# dac-power.net
KiCad netlist of a schematic drawn in Altium Designer
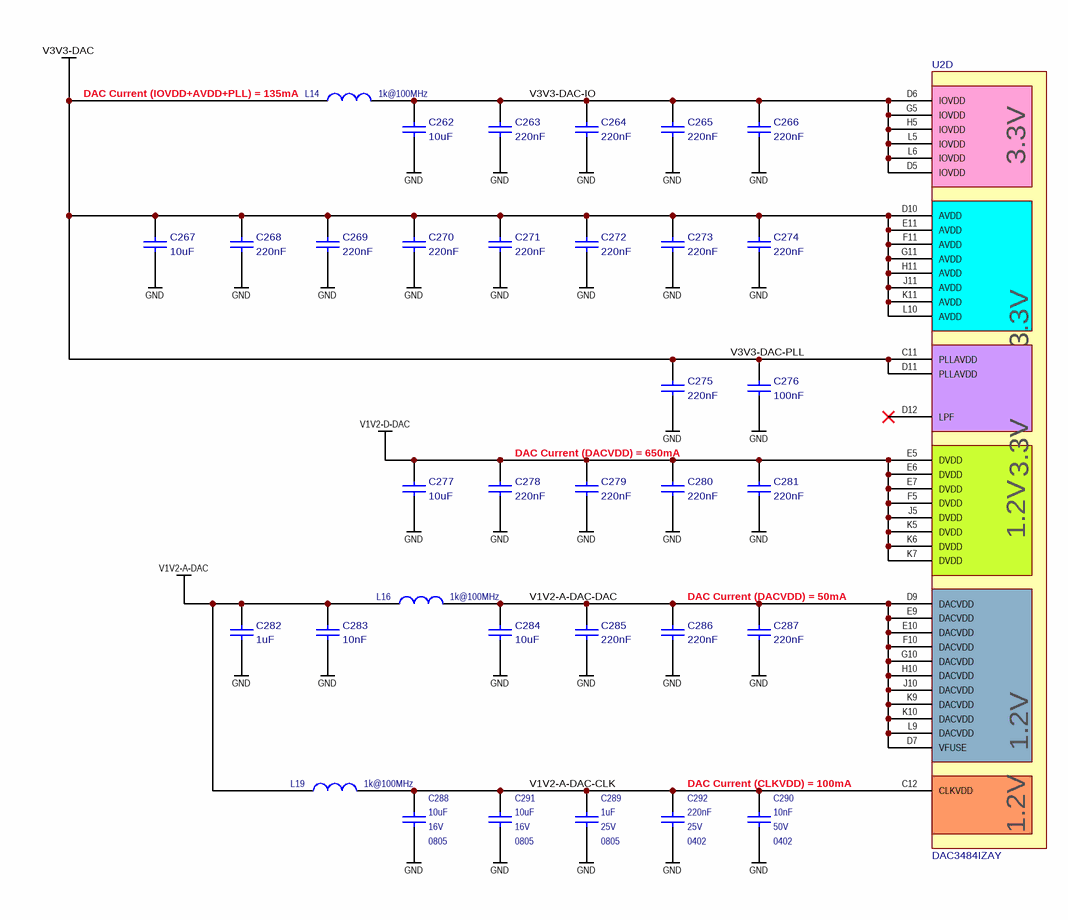
[diagram p0: dac-power.SchDoc]

(export (version "E")
  (design (tool "Eeschema 10.0.6"))
  (components
    (comp (ref "C262")
      (value "10uF")
      (footprint "CAPC200X125X145L45N")
      (description "Ceramic Capacitor 10uF ±10% 16V X7R 0805")
      (fields (field (name "MANUFACTURER") "Samsung") (field (name "TOLERANCE") "±10%"))
      (libsource (lib "capacitors") (part "CAP"))
    )
    (comp (ref "C263")
      (value "220nF")
      (footprint "CAPC100X50X55L25N")
      (description "Ceramic Capacitor 220nF ±10% 25V X7R 0402")
      (fields (field (name "MANUFACTURER") "TDK") (field (name "TOLERANCE") "±10%"))
      (libsource (lib "capacitors") (part "CAP"))
    )
    (comp (ref "C264")
      (value "220nF")
      (footprint "CAPC100X50X55L25N")
      (description "Ceramic Capacitor 220nF ±10% 25V X7R 0402")
      (fields (field (name "MANUFACTURER") "TDK") (field (name "TOLERANCE") "±10%"))
      (libsource (lib "capacitors") (part "CAP"))
    )
    (comp (ref "C265")
      (value "220nF")
      (footprint "CAPC100X50X55L25N")
      (description "Ceramic Capacitor 220nF ±10% 25V X7R 0402")
      (fields (field (name "MANUFACTURER") "TDK") (field (name "TOLERANCE") "±10%"))
      (libsource (lib "capacitors") (part "CAP"))
    )
    (comp (ref "C266")
      (value "220nF")
      (footprint "CAPC100X50X55L25N")
      (description "Ceramic Capacitor 220nF ±10% 25V X7R 0402")
      (fields (field (name "MANUFACTURER") "TDK") (field (name "TOLERANCE") "±10%"))
      (libsource (lib "capacitors") (part "CAP"))
    )
    (comp (ref "C267")
      (value "10uF")
      (footprint "CAPC200X125X145L45N")
      (description "Ceramic Capacitor 10uF ±10% 16V X7R 0805")
      (fields (field (name "MANUFACTURER") "Samsung") (field (name "TOLERANCE") "±10%"))
      (libsource (lib "capacitors") (part "CAP"))
    )
    (comp (ref "C268")
      (value "220nF")
      (footprint "CAPC100X50X55L25N")
      (description "Ceramic Capacitor 220nF ±10% 25V X7R 0402")
      (fields (field (name "MANUFACTURER") "TDK") (field (name "TOLERANCE") "±10%"))
      (libsource (lib "capacitors") (part "CAP"))
    )
    (comp (ref "C269")
      (value "220nF")
      (footprint "CAPC100X50X55L25N")
      (description "Ceramic Capacitor 220nF ±10% 25V X7R 0402")
      (fields (field (name "MANUFACTURER") "TDK") (field (name "TOLERANCE") "±10%"))
      (libsource (lib "capacitors") (part "CAP"))
    )
    (comp (ref "C270")
      (value "220nF")
      (footprint "CAPC100X50X55L25N")
      (description "Ceramic Capacitor 220nF ±10% 25V X7R 0402")
      (fields (field (name "MANUFACTURER") "TDK") (field (name "TOLERANCE") "±10%"))
      (libsource (lib "capacitors") (part "CAP"))
    )
    (comp (ref "C271")
      (value "220nF")
      (footprint "CAPC100X50X55L25N")
      (description "Ceramic Capacitor 220nF ±10% 25V X7R 0402")
      (fields (field (name "MANUFACTURER") "TDK") (field (name "TOLERANCE") "±10%"))
      (libsource (lib "capacitors") (part "CAP"))
    )
    (comp (ref "C272")
      (value "220nF")
      (footprint "CAPC100X50X55L25N")
      (description "Ceramic Capacitor 220nF ±10% 25V X7R 0402")
      (fields (field (name "MANUFACTURER") "TDK") (field (name "TOLERANCE") "±10%"))
      (libsource (lib "capacitors") (part "CAP"))
    )
    (comp (ref "C273")
      (value "220nF")
      (footprint "CAPC100X50X55L25N")
      (description "Ceramic Capacitor 220nF ±10% 25V X7R 0402")
      (fields (field (name "MANUFACTURER") "TDK") (field (name "TOLERANCE") "±10%"))
      (libsource (lib "capacitors") (part "CAP"))
    )
    (comp (ref "C274")
      (value "220nF")
      (footprint "CAPC100X50X55L25N")
      (description "Ceramic Capacitor 220nF ±10% 25V X7R 0402")
      (fields (field (name "MANUFACTURER") "TDK") (field (name "TOLERANCE") "±10%"))
      (libsource (lib "capacitors") (part "CAP"))
    )
    (comp (ref "C275")
      (value "220nF")
      (footprint "CAPC100X50X55L25N")
      (description "Ceramic Capacitor 220nF ±10% 25V X7R 0402")
      (fields (field (name "MANUFACTURER") "TDK") (field (name "TOLERANCE") "±10%"))
      (libsource (lib "capacitors") (part "CAP"))
    )
    (comp (ref "C276")
      (value "100nF")
      (footprint "CAPC100X50X55L25N")
      (description "Ceramic Capacitor 100nF ±10% 25V X7R 0402")
      (fields (field (name "MANUFACTURER") "Yageo") (field (name "TOLERANCE") "±10%"))
      (libsource (lib "capacitors") (part "CAP"))
    )
    (comp (ref "C277")
      (value "10uF")
      (footprint "CAPC200X125X145L45N")
      (description "Ceramic Capacitor 10uF ±10% 16V X7R 0805")
      (fields (field (name "MANUFACTURER") "Samsung") (field (name "TOLERANCE") "±10%"))
      (libsource (lib "capacitors") (part "CAP"))
    )
    (comp (ref "C278")
      (value "220nF")
      (footprint "CAPC100X50X55L25N")
      (description "Ceramic Capacitor 220nF ±10% 25V X7R 0402")
      (fields (field (name "MANUFACTURER") "TDK") (field (name "TOLERANCE") "±10%"))
      (libsource (lib "capacitors") (part "CAP"))
    )
    (comp (ref "C279")
      (value "220nF")
      (footprint "CAPC100X50X55L25N")
      (description "Ceramic Capacitor 220nF ±10% 25V X7R 0402")
      (fields (field (name "MANUFACTURER") "TDK") (field (name "TOLERANCE") "±10%"))
      (libsource (lib "capacitors") (part "CAP"))
    )
    (comp (ref "C280")
      (value "220nF")
      (footprint "CAPC100X50X55L25N")
      (description "Ceramic Capacitor 220nF ±10% 25V X7R 0402")
      (fields (field (name "MANUFACTURER") "TDK") (field (name "TOLERANCE") "±10%"))
      (libsource (lib "capacitors") (part "CAP"))
    )
    (comp (ref "C281")
      (value "220nF")
      (footprint "CAPC100X50X55L25N")
      (description "Ceramic Capacitor 220nF ±10% 25V X7R 0402")
      (fields (field (name "MANUFACTURER") "TDK") (field (name "TOLERANCE") "±10%"))
      (libsource (lib "capacitors") (part "CAP"))
    )
    (comp (ref "C282")
      (value "1uF")
      (footprint "CAPC200X125X145L45N")
      (description "Ceramic Capacitor 1uF ±10% 25V X7R 0805")
      (fields (field (name "MANUFACTURER") "Taiyo Yuden") (field (name "TOLERANCE") "±10%"))
      (libsource (lib "capacitors") (part "CAP"))
    )
    (comp (ref "C283")
      (value "10nF")
      (footprint "CAPC100X50X55L25N")
      (description "Ceramic Capacitor 10nF ±10% 50V X7R 0402")
      (fields (field (name "MANUFACTURER") "Murata") (field (name "TOLERANCE") "±10%"))
      (libsource (lib "capacitors") (part "CAP"))
    )
    (comp (ref "C284")
      (value "10uF")
      (footprint "CAPC200X125X145L45N")
      (description "Ceramic Capacitor 10uF ±10% 16V X7R 0805")
      (fields (field (name "MANUFACTURER") "Samsung") (field (name "TOLERANCE") "±10%"))
      (libsource (lib "capacitors") (part "CAP"))
    )
    (comp (ref "C285")
      (value "220nF")
      (footprint "CAPC100X50X55L25N")
      (description "Ceramic Capacitor 220nF ±10% 25V X7R 0402")
      (fields (field (name "MANUFACTURER") "TDK") (field (name "TOLERANCE") "±10%"))
      (libsource (lib "capacitors") (part "CAP"))
    )
    (comp (ref "C286")
      (value "220nF")
      (footprint "CAPC100X50X55L25N")
      (description "Ceramic Capacitor 220nF ±10% 25V X7R 0402")
      (fields (field (name "MANUFACTURER") "TDK") (field (name "TOLERANCE") "±10%"))
      (libsource (lib "capacitors") (part "CAP"))
    )
    (comp (ref "C287")
      (value "220nF")
      (footprint "CAPC100X50X55L25N")
      (description "Ceramic Capacitor 220nF ±10% 25V X7R 0402")
      (fields (field (name "MANUFACTURER") "TDK") (field (name "TOLERANCE") "±10%"))
      (libsource (lib "capacitors") (part "CAP"))
    )
    (comp (ref "C288")
      (value "10uF")
      (footprint "generic:CAPC2012X145N")
      (description "Ceramic Capacitor 10uF ±20% 16V X7R 0805")
      (fields
        (field (name "MANUFACTURER") "Taiyo Yuden")
        (field (name "VOLTAGE") "16V")
        (field (name "PACKAGE") "0805")
        (field (name "TOLERANCE") "±20%")
      )
      (libsource (lib "generic") (part "CAP 0603"))
    )
    (comp (ref "C289")
      (value "1uF")
      (footprint "CAPC200X125X145L45N")
      (description "Ceramic Capacitor 1uF ±10% 25V X7R 0805")
      (fields
        (field (name "VOLTAGE") "25V")
        (field (name "MANUFACTURER") "Taiyo Yuden")
        (field (name "PACKAGE") "0805")
        (field (name "TOLERANCE") "±10%")
      )
      (libsource (lib "Graviton") (part "CAP 0402"))
    )
    (comp (ref "C290")
      (value "10nF")
      (footprint "CAPC100X50X55L25N")
      (description "Ceramic Capacitor 10nF ±10% 50V X7R 0402")
      (fields
        (field (name "VOLTAGE") "50V")
        (field (name "MANUFACTURER") "Murata")
        (field (name "PACKAGE") "0402")
        (field (name "TOLERANCE") "±10%")
      )
      (libsource (lib "Graviton") (part "CAP 0402"))
    )
    (comp (ref "C291")
      (value "10uF")
      (footprint "generic:CAPC2012X145N")
      (description "Ceramic Capacitor 10uF ±20% 16V X7R 0805")
      (fields
        (field (name "MANUFACTURER") "Taiyo Yuden")
        (field (name "VOLTAGE") "16V")
        (field (name "PACKAGE") "0805")
        (field (name "TOLERANCE") "±20%")
      )
      (libsource (lib "generic") (part "CAP 0603"))
    )
    (comp (ref "C292")
      (value "220nF")
      (footprint "CAPC100X50X55L25N")
      (description "Ceramic Capacitor 220nF ±10% 25V X7R 0402")
      (fields
        (field (name "VOLTAGE") "25V")
        (field (name "MANUFACTURER") "TDK")
        (field (name "PACKAGE") "0402")
        (field (name "TOLERANCE") "±10%")
      )
      (libsource (lib "Graviton") (part "CAP 0402"))
    )
    (comp (ref "L14")
      (value "1k@100MHz")
      (footprint "generic:1806")
      (description "Ferrite Bead 1k@100MHz 1.5A 1806")
      (fields (field (name "MANUFACTURER") "Murata") (field (name "Comment") "BLM41PG102SN1L"))
      (libsource (lib "*") (part "INDUCTANCE1"))
    )
    (comp (ref "L16")
      (value "1k@100MHz")
      (footprint "generic:1806")
      (description "Ferrite Bead 1k@100MHz 1.5A 1806")
      (fields (field (name "MANUFACTURER") "Murata") (field (name "Comment") "BLM41PG102SN1L"))
      (libsource (lib "*") (part "INDUCTANCE1"))
    )
    (comp (ref "L19")
      (value "1k@100MHz")
      (footprint "generic:1806")
      (description "Ferrite Bead 1k@100MHz 1.5A 1806")
      (fields (field (name "MANUFACTURER") "Murata") (field (name "Comment") "BLM41PG102SN1L"))
      (libsource (lib "*") (part "INDUCTANCE1"))
    )
    (comp (ref "U2")
      (value "DAC3484IZAY")
      (footprint "ZAY-BGA-196")
      (description "High Speed Quad DAC, 16-bit, 1.25GSPS")
      (fields (field (name "MANUFACTURER") "Texas Instruments"))
      (libsource (lib "ti") (part "DAC3484IZAY"))
    )
  )
  (nets
    (net (code "1") (name "/V1V2-A-DAC-CLK") (class "Default")
      (node (ref "C288") (pin "2") (pinfunction "2_2") (pintype "passive"))
      (node (ref "C289") (pin "2") (pinfunction "2_2") (pintype "passive"))
      (node (ref "C290") (pin "2") (pinfunction "2_2") (pintype "passive"))
      (node (ref "C291") (pin "2") (pinfunction "2_2") (pintype "passive"))
      (node (ref "C292") (pin "2") (pinfunction "2_2") (pintype "passive"))
      (node (ref "L19") (pin "2") (pinfunction "2_2") (pintype "passive"))
      (node (ref "U2") (pin "C12") (pinfunction "CLKVDD_C12") (pintype "power_in"))
    )
    (net (code "2") (name "/V1V2-A-DAC-DAC") (class "Default")
      (node (ref "C284") (pin "1") (pinfunction "1_1") (pintype "passive"))
      (node (ref "C285") (pin "1") (pinfunction "1_1") (pintype "passive"))
      (node (ref "C286") (pin "1") (pinfunction "1_1") (pintype "passive"))
      (node (ref "C287") (pin "1") (pinfunction "1_1") (pintype "passive"))
      (node (ref "L16") (pin "2") (pinfunction "2_2") (pintype "passive"))
      (node (ref "U2") (pin "D7") (pinfunction "VFUSE_D7") (pintype "passive"))
      (node (ref "U2") (pin "D9") (pinfunction "DACVDD_D9") (pintype "power_in"))
      (node (ref "U2") (pin "E10") (pinfunction "DACVDD_E10") (pintype "power_in"))
      (node (ref "U2") (pin "E9") (pinfunction "DACVDD_E9") (pintype "power_in"))
      (node (ref "U2") (pin "F10") (pinfunction "DACVDD_F10") (pintype "power_in"))
      (node (ref "U2") (pin "G10") (pinfunction "DACVDD_G10") (pintype "power_in"))
      (node (ref "U2") (pin "H10") (pinfunction "DACVDD_H10") (pintype "power_in"))
      (node (ref "U2") (pin "J10") (pinfunction "DACVDD_J10") (pintype "power_in"))
      (node (ref "U2") (pin "K10") (pinfunction "DACVDD_K10") (pintype "power_in"))
      (node (ref "U2") (pin "K9") (pinfunction "DACVDD_K9") (pintype "power_in"))
      (node (ref "U2") (pin "L9") (pinfunction "DACVDD_L9") (pintype "power_in"))
    )
    (net (code "3") (name "/V3V3-DAC-IO") (class "Default")
      (node (ref "C262") (pin "1") (pinfunction "1_1") (pintype "passive"))
      (node (ref "C263") (pin "1") (pinfunction "1_1") (pintype "passive"))
      (node (ref "C264") (pin "1") (pinfunction "1_1") (pintype "passive"))
      (node (ref "C265") (pin "1") (pinfunction "1_1") (pintype "passive"))
      (node (ref "C266") (pin "1") (pinfunction "1_1") (pintype "passive"))
      (node (ref "L14") (pin "2") (pinfunction "2_2") (pintype "passive"))
      (node (ref "U2") (pin "D5") (pinfunction "IOVDD_D5") (pintype "power_in"))
      (node (ref "U2") (pin "D6") (pinfunction "IOVDD_D6") (pintype "power_in"))
      (node (ref "U2") (pin "G5") (pinfunction "IOVDD_G5") (pintype "power_in"))
      (node (ref "U2") (pin "H5") (pinfunction "IOVDD_H5") (pintype "power_in"))
      (node (ref "U2") (pin "L5") (pinfunction "IOVDD_L5") (pintype "power_in"))
      (node (ref "U2") (pin "L6") (pinfunction "IOVDD_L6") (pintype "power_in"))
    )
    (net (code "4") (name "GND") (class "Default")
      (node (ref "C262") (pin "2") (pinfunction "2_2") (pintype "passive"))
      (node (ref "C263") (pin "2") (pinfunction "2_2") (pintype "passive"))
      (node (ref "C264") (pin "2") (pinfunction "2_2") (pintype "passive"))
      (node (ref "C265") (pin "2") (pinfunction "2_2") (pintype "passive"))
      (node (ref "C266") (pin "2") (pinfunction "2_2") (pintype "passive"))
      (node (ref "C267") (pin "2") (pinfunction "2_2") (pintype "passive"))
      (node (ref "C268") (pin "2") (pinfunction "2_2") (pintype "passive"))
      (node (ref "C269") (pin "2") (pinfunction "2_2") (pintype "passive"))
      (node (ref "C270") (pin "2") (pinfunction "2_2") (pintype "passive"))
      (node (ref "C271") (pin "2") (pinfunction "2_2") (pintype "passive"))
      (node (ref "C272") (pin "2") (pinfunction "2_2") (pintype "passive"))
      (node (ref "C273") (pin "2") (pinfunction "2_2") (pintype "passive"))
      (node (ref "C274") (pin "2") (pinfunction "2_2") (pintype "passive"))
      (node (ref "C275") (pin "2") (pinfunction "2_2") (pintype "passive"))
      (node (ref "C276") (pin "2") (pinfunction "2_2") (pintype "passive"))
      (node (ref "C277") (pin "2") (pinfunction "2_2") (pintype "passive"))
      (node (ref "C278") (pin "2") (pinfunction "2_2") (pintype "passive"))
      (node (ref "C279") (pin "2") (pinfunction "2_2") (pintype "passive"))
      (node (ref "C280") (pin "2") (pinfunction "2_2") (pintype "passive"))
      (node (ref "C281") (pin "2") (pinfunction "2_2") (pintype "passive"))
      (node (ref "C282") (pin "2") (pinfunction "2_2") (pintype "passive"))
      (node (ref "C283") (pin "2") (pinfunction "2_2") (pintype "passive"))
      (node (ref "C284") (pin "2") (pinfunction "2_2") (pintype "passive"))
      (node (ref "C285") (pin "2") (pinfunction "2_2") (pintype "passive"))
      (node (ref "C286") (pin "2") (pinfunction "2_2") (pintype "passive"))
      (node (ref "C287") (pin "2") (pinfunction "2_2") (pintype "passive"))
      (node (ref "C288") (pin "1") (pinfunction "1_1") (pintype "passive"))
      (node (ref "C289") (pin "1") (pinfunction "1_1") (pintype "passive"))
      (node (ref "C290") (pin "1") (pinfunction "1_1") (pintype "passive"))
      (node (ref "C291") (pin "1") (pinfunction "1_1") (pintype "passive"))
      (node (ref "C292") (pin "1") (pinfunction "1_1") (pintype "passive"))
    )
    (net (code "5") (name "V1V2-A-DAC") (class "Default")
      (node (ref "C282") (pin "1") (pinfunction "1_1") (pintype "passive"))
      (node (ref "C283") (pin "1") (pinfunction "1_1") (pintype "passive"))
      (node (ref "L16") (pin "1") (pinfunction "1_1") (pintype "passive"))
      (node (ref "L19") (pin "1") (pinfunction "1_1") (pintype "passive"))
    )
    (net (code "6") (name "V1V2-D-DAC") (class "Default")
      (node (ref "C277") (pin "1") (pinfunction "1_1") (pintype "passive"))
      (node (ref "C278") (pin "1") (pinfunction "1_1") (pintype "passive"))
      (node (ref "C279") (pin "1") (pinfunction "1_1") (pintype "passive"))
      (node (ref "C280") (pin "1") (pinfunction "1_1") (pintype "passive"))
      (node (ref "C281") (pin "1") (pinfunction "1_1") (pintype "passive"))
      (node (ref "U2") (pin "E5") (pinfunction "DVDD_E5") (pintype "power_in"))
      (node (ref "U2") (pin "E6") (pinfunction "DVDD_E6") (pintype "power_in"))
      (node (ref "U2") (pin "E7") (pinfunction "DVDD_E7") (pintype "power_in"))
      (node (ref "U2") (pin "F5") (pinfunction "DVDD_F5") (pintype "power_in"))
      (node (ref "U2") (pin "J5") (pinfunction "DVDD_J5") (pintype "power_in"))
      (node (ref "U2") (pin "K5") (pinfunction "DVDD_K5") (pintype "power_in"))
      (node (ref "U2") (pin "K6") (pinfunction "DVDD_K6") (pintype "power_in"))
      (node (ref "U2") (pin "K7") (pinfunction "DVDD_K7") (pintype "power_in"))
    )
    (net (code "7") (name "V3V3-DAC") (class "Default")
      (node (ref "C267") (pin "1") (pinfunction "1_1") (pintype "passive"))
      (node (ref "C268") (pin "1") (pinfunction "1_1") (pintype "passive"))
      (node (ref "C269") (pin "1") (pinfunction "1_1") (pintype "passive"))
      (node (ref "C270") (pin "1") (pinfunction "1_1") (pintype "passive"))
      (node (ref "C271") (pin "1") (pinfunction "1_1") (pintype "passive"))
      (node (ref "C272") (pin "1") (pinfunction "1_1") (pintype "passive"))
      (node (ref "C273") (pin "1") (pinfunction "1_1") (pintype "passive"))
      (node (ref "C274") (pin "1") (pinfunction "1_1") (pintype "passive"))
      (node (ref "C275") (pin "1") (pinfunction "1_1") (pintype "passive"))
      (node (ref "C276") (pin "1") (pinfunction "1_1") (pintype "passive"))
      (node (ref "L14") (pin "1") (pinfunction "1_1") (pintype "passive"))
      (node (ref "U2") (pin "C11") (pinfunction "PLLAVDD_C11") (pintype "power_in"))
      (node (ref "U2") (pin "D10") (pinfunction "AVDD_D10") (pintype "power_in"))
      (node (ref "U2") (pin "D11") (pinfunction "PLLAVDD_D11") (pintype "power_in"))
      (node (ref "U2") (pin "E11") (pinfunction "AVDD_E11") (pintype "power_in"))
      (node (ref "U2") (pin "F11") (pinfunction "AVDD_F11") (pintype "power_in"))
      (node (ref "U2") (pin "G11") (pinfunction "AVDD_G11") (pintype "power_in"))
      (node (ref "U2") (pin "H11") (pinfunction "AVDD_H11") (pintype "power_in"))
      (node (ref "U2") (pin "J11") (pinfunction "AVDD_J11") (pintype "power_in"))
      (node (ref "U2") (pin "K11") (pinfunction "AVDD_K11") (pintype "power_in"))
      (node (ref "U2") (pin "L10") (pinfunction "AVDD_L10") (pintype "power_in"))
    )
    (net (code "8") (name "unconnected-(U2D-LPF-PadD12)") (class "Default")
      (node (ref "U2") (pin "D12") (pinfunction "LPF_D12") (pintype "passive+no_connect"))
    )
  )
)
